# CH32V307VCT6-R1.net
KiCad netlist of a schematic drawn in Altium Designer
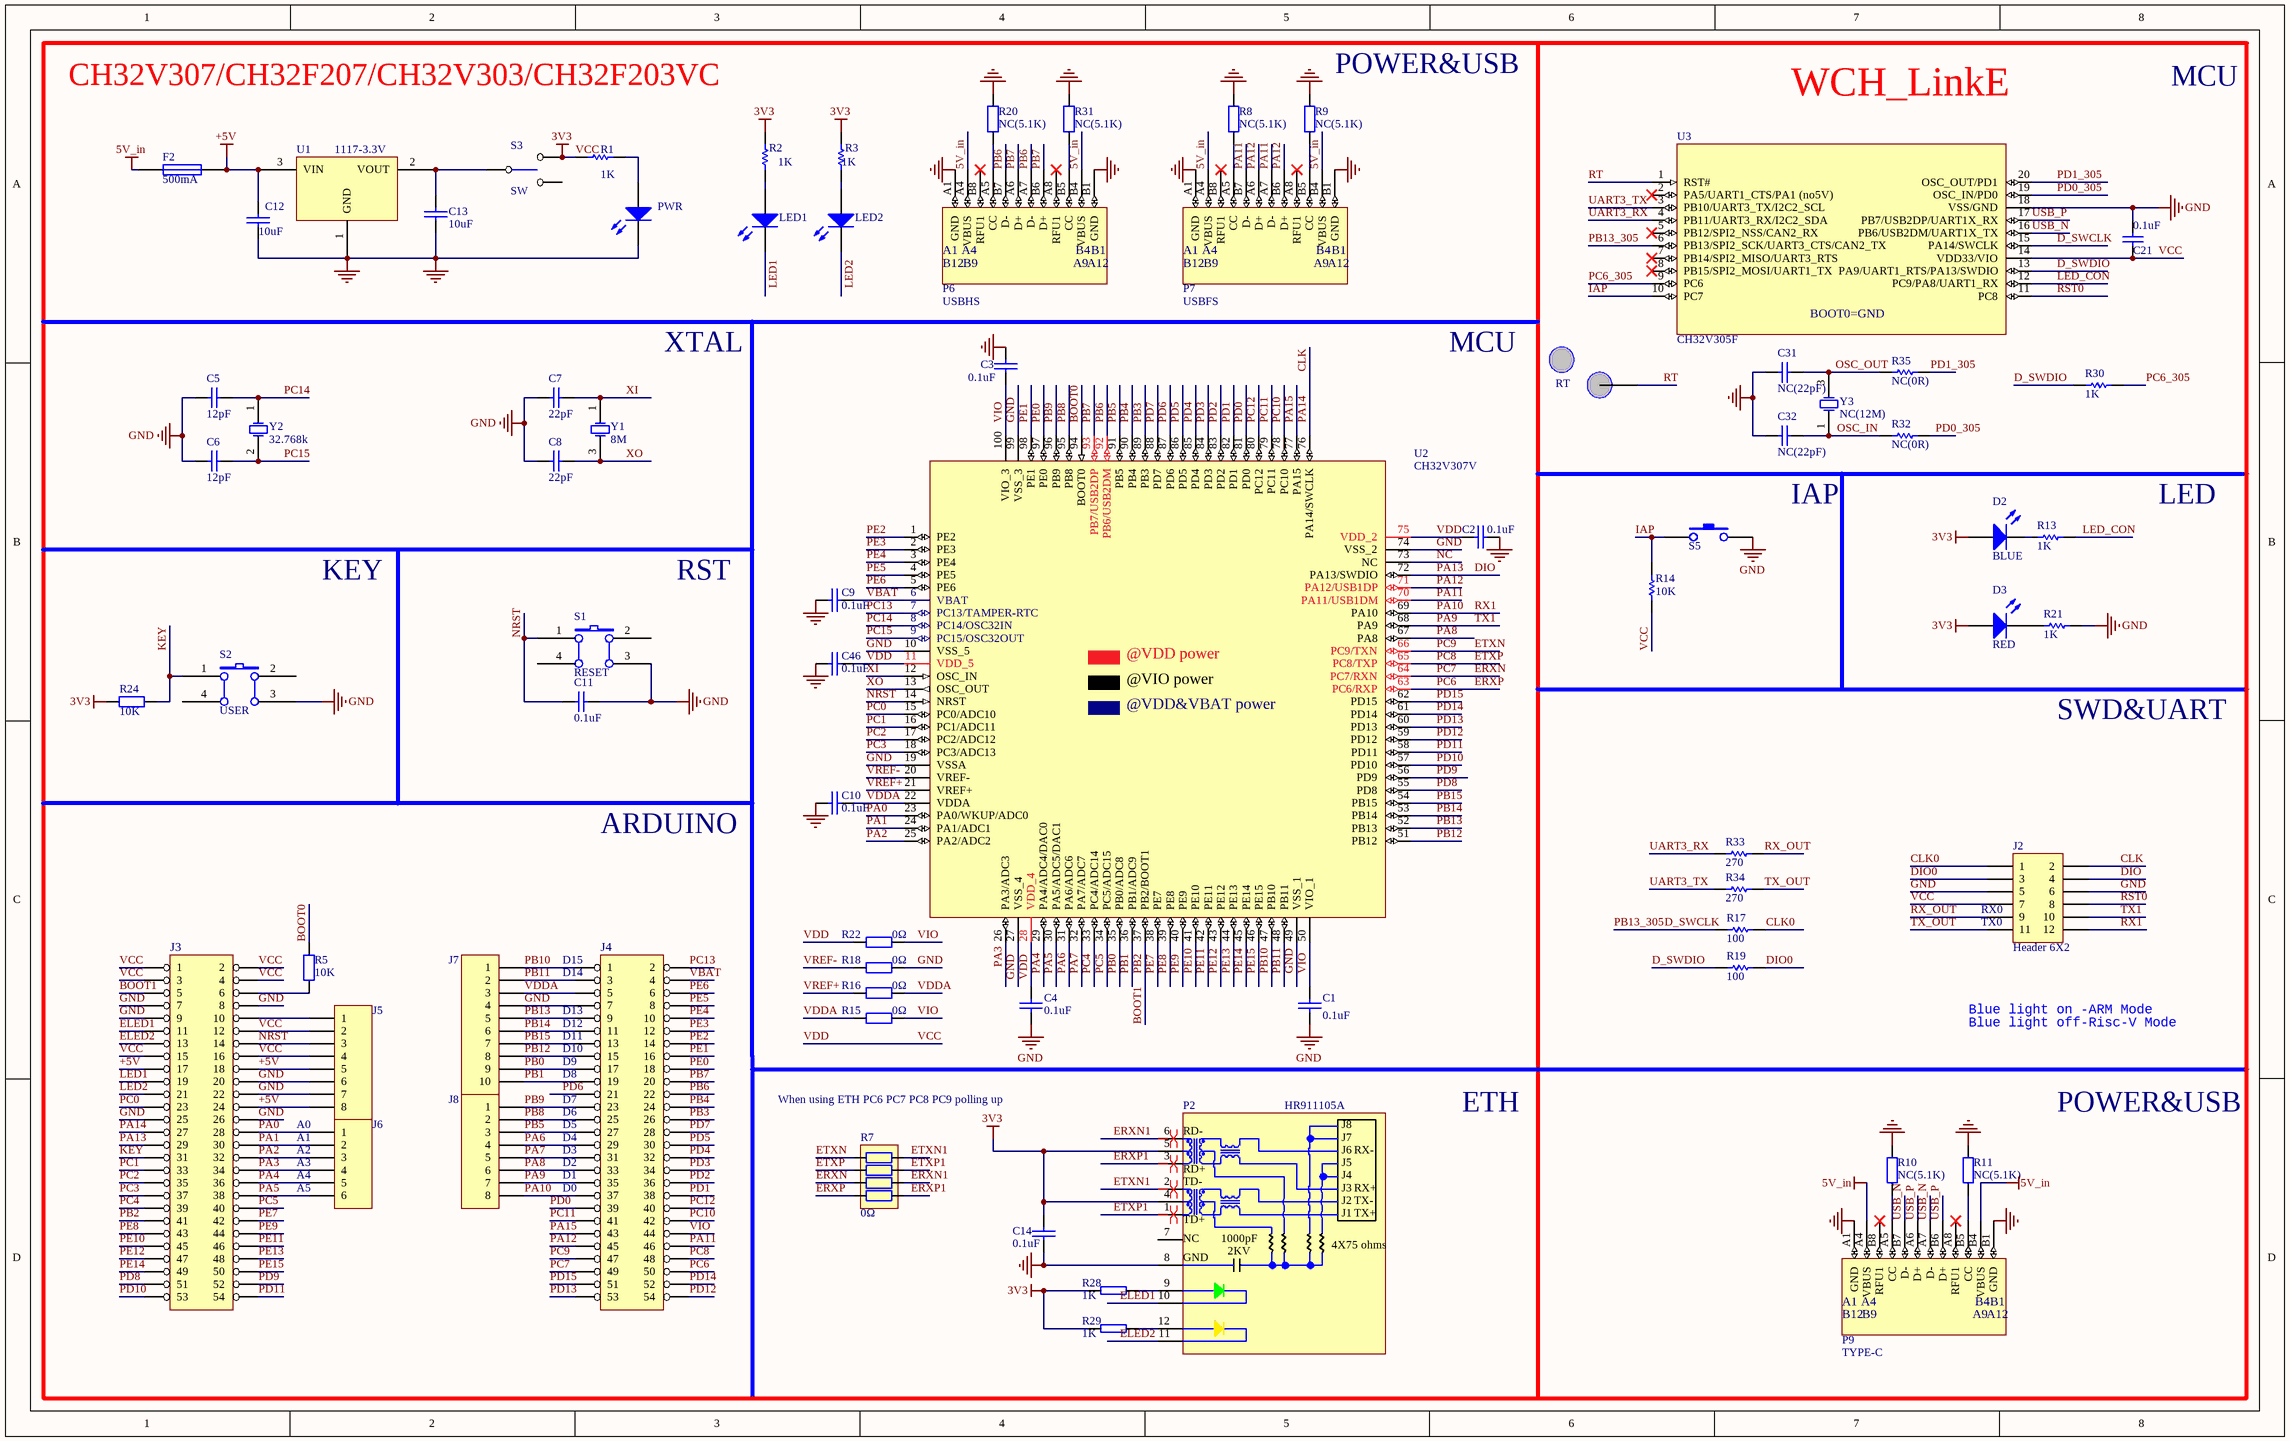
[diagram p0: CH32V307VCT6-R1.SchDoc]

(export (version "E")
  (design (tool "Eeschema 10.0.6"))
  (components
    (comp (ref "C1")
      (value "0.1uF")
      (footprint "0603_C")
      (description "Capacitor")
      (libsource (lib "*") (part "CAP"))
    )
    (comp (ref "C2")
      (value "0.1uF")
      (footprint "0603_C")
      (description "Capacitor")
      (libsource (lib "*") (part "CAP"))
    )
    (comp (ref "C3")
      (value "0.1uF")
      (footprint "0603_C")
      (description "Capacitor")
      (libsource (lib "*") (part "CAP"))
    )
    (comp (ref "C4")
      (value "0.1uF")
      (footprint "0603_C")
      (description "Capacitor")
      (libsource (lib "*") (part "CAP"))
    )
    (comp (ref "C5")
      (value "12pF")
      (footprint "0603_C")
      (description "Capacitor")
      (libsource (lib "Miscellaneous Devices") (part "Cap"))
    )
    (comp (ref "C6")
      (value "12pF")
      (footprint "0603_C")
      (description "Capacitor")
      (libsource (lib "Miscellaneous Devices") (part "Cap"))
    )
    (comp (ref "C7")
      (value "22pF")
      (footprint "0603_C")
      (description "Capacitor")
      (libsource (lib "Miscellaneous Devices") (part "Cap"))
    )
    (comp (ref "C8")
      (value "22pF")
      (footprint "0603_C")
      (description "Capacitor")
      (libsource (lib "Miscellaneous Devices") (part "Cap"))
    )
    (comp (ref "C9")
      (value "0.1uF")
      (footprint "0603_C")
      (description "Capacitor")
      (libsource (lib "*") (part "CAP"))
    )
    (comp (ref "C10")
      (value "0.1uF")
      (footprint "0603_C")
      (description "Capacitor")
      (libsource (lib "*") (part "CAP"))
    )
    (comp (ref "C11")
      (value "0.1uF")
      (footprint "0603_C")
      (description "Capacitor")
      (libsource (lib "Miscellaneous Devices") (part "Cap"))
    )
    (comp (ref "C12")
      (value "10uF")
      (footprint "3216_C")
      (description "Capacitor")
      (libsource (lib "*") (part "CAP"))
    )
    (comp (ref "C13")
      (value "10uF")
      (footprint "3216_C")
      (description "Capacitor")
      (libsource (lib "*") (part "CAP"))
    )
    (comp (ref "C14")
      (value "0.1uF")
      (footprint "0603_C")
      (description "Capacitor")
      (libsource (lib "*") (part "CAP"))
    )
    (comp (ref "C21")
      (value "0.1uF")
      (footprint "0603_C")
      (description "Capacitor")
      (libsource (lib "Miscellaneous Devices") (part "Cap"))
    )
    (comp (ref "C31")
      (value "NC(22pF)")
      (footprint "0603_C")
      (description "Capacitor")
      (libsource (lib "*") (part "Cap"))
    )
    (comp (ref "C32")
      (value "NC(22pF)")
      (footprint "0603_C")
      (description "Capacitor")
      (libsource (lib "*") (part "Cap"))
    )
    (comp (ref "C46")
      (value "0.1uF")
      (footprint "0603_C")
      (description "Capacitor")
      (libsource (lib "*") (part "CAP"))
    )
    (comp (ref "D2")
      (value "BLUE")
      (footprint "0603+")
      (description "Typical RED, GREEN, YELLOW, AMBER GaAs LED")
      (libsource (lib "MYLIB") (part "D0603"))
    )
    (comp (ref "D3")
      (value "RED")
      (footprint "0603+")
      (description "Typical RED, GREEN, YELLOW, AMBER GaAs LED")
      (libsource (lib "MYLIB") (part "D0603"))
    )
    (comp (ref "F2")
      (value "500mA")
      (footprint "0805")
      (description "Fuse")
      (libsource (lib "*") (part "FUSE1"))
    )
    (comp (ref "J2")
      (value "Header 6X2")
      (footprint "IDC12-2.54mm")
      (description "Header, 6-Pin, Dual row")
      (libsource (lib "Miscellaneous Connectors") (part "Header 6X2"))
    )
    (comp (ref "J3")
      (value "HEADER 27x2")
      (footprint "MYPCB:IDC54-2.54MM")
      (description "Header, 27-Pin, Dual row")
      (libsource (lib "wch_sch_others") (part "HEADER 27x2"))
    )
    (comp (ref "J4")
      (value "HEADER 27x2")
      (footprint "MYPCB:IDC54-2.54MM")
      (description "Header, 27-Pin, Dual row")
      (libsource (lib "wch_sch_others") (part "HEADER 27x2"))
    )
    (comp (ref "J5")
      (value "Header 8")
      (footprint "SIP8-2.54mm")
      (description "Header, 8-Pin")
      (libsource (lib "Miscellaneous Connectors") (part "Header 8"))
    )
    (comp (ref "J6")
      (value "Header 6")
      (footprint "SIP6-2.54MM")
      (description "Header, 6-Pin")
      (libsource (lib "Miscellaneous Connectors") (part "Header 6"))
    )
    (comp (ref "J7")
      (value "Header 10")
      (footprint "SIP10-2.54mm")
      (description "Header, 10-Pin")
      (libsource (lib "Miscellaneous Connectors") (part "Header 10"))
    )
    (comp (ref "J8")
      (value "Header 8")
      (footprint "SIP8-2.54mm")
      (description "Header, 8-Pin")
      (libsource (lib "") (part "Header 8_1"))
    )
    (comp (ref "LED1")
      (value "LED1   blue")
      (footprint "0603+")
      (description "Typical INFRARED GaAs LED")
      (libsource (lib "Miscellaneous Devices") (part "LED0"))
    )
    (comp (ref "LED2")
      (value "LED2  blue")
      (footprint "0603+")
      (description "Typical INFRARED GaAs LED")
      (libsource (lib "Miscellaneous Devices") (part "LED0"))
    )
    (comp (ref "P2") (value "HR911105A") (footprint "HR911105A") (libsource (lib "*") (part "HR911105A")))
    (comp (ref "P6")
      (value "USBHS")
      (footprint "TYPE-C-Receptacle-2.0")
      (libsource (lib "*") (part "TYPE-C1"))
    )
    (comp (ref "P7")
      (value "USBFS")
      (footprint "TYPE-C-Receptacle-2.0")
      (libsource (lib "*") (part "TYPE-C1"))
    )
    (comp (ref "P9")
      (value "TYPE-C")
      (footprint "TYPE-C-Receptacle-2.0")
      (libsource (lib "*") (part "TYPE-C1"))
    )
    (comp (ref "PWR")
      (value "POWER  red")
      (footprint "0603+")
      (description "Typical INFRARED GaAs LED")
      (libsource (lib "Miscellaneous Devices") (part "LED0"))
    )
    (comp (ref "R1")
      (value "1K")
      (footprint "0603")
      (description "Semiconductor Resistor")
      (libsource (lib "Miscellaneous Devices") (part "Res Semi"))
    )
    (comp (ref "R2")
      (value "1K")
      (footprint "0603")
      (description "Semiconductor Resistor")
      (libsource (lib "Miscellaneous Devices") (part "Res Semi"))
    )
    (comp (ref "R3")
      (value "1K")
      (footprint "0603")
      (description "Semiconductor Resistor")
      (libsource (lib "Miscellaneous Devices") (part "Res Semi"))
    )
    (comp (ref "R5")
      (value "10K")
      (footprint "0603")
      (description "Resistor")
      (libsource (lib "") (part "Res2_2"))
    )
    (comp (ref "R7")
      (value "0Ω")
      (footprint "RCA-8P4R-0603")
      (description "贴片网络排阻")
      (libsource (lib "wch_sch_others") (part "R-8P4R"))
    )
    (comp (ref "R8")
      (value "NC(5.1K)")
      (footprint "0603")
      (description "Resistor")
      (libsource (lib "") (part "Res2_1"))
    )
    (comp (ref "R9")
      (value "NC(5.1K)")
      (footprint "0603")
      (description "Resistor")
      (libsource (lib "") (part "Res2_1"))
    )
    (comp (ref "R10")
      (value "NC(5.1K)")
      (footprint "0603")
      (description "Resistor")
      (libsource (lib "") (part "Res2_2"))
    )
    (comp (ref "R11")
      (value "NC(5.1K)")
      (footprint "0603")
      (description "Resistor")
      (libsource (lib "") (part "Res2_2"))
    )
    (comp (ref "R13")
      (value "1K")
      (footprint "0603")
      (description "Resistor")
      (libsource (lib "MYLIB") (part "0603-1"))
    )
    (comp (ref "R14")
      (value "10K")
      (footprint "0603")
      (description "Resistor")
      (libsource (lib "MYLIB") (part "0603-1"))
    )
    (comp (ref "R15")
      (value "0Ω")
      (footprint "0603")
      (description "Resistor")
      (libsource (lib "Miscellaneous Devices") (part "Res2"))
    )
    (comp (ref "R16")
      (value "0Ω")
      (footprint "0603")
      (description "Resistor")
      (libsource (lib "Miscellaneous Devices") (part "Res2"))
    )
    (comp (ref "R17")
      (value "100")
      (footprint "0603")
      (description "Resistor")
      (libsource (lib "MYLIB") (part "0603-1"))
    )
    (comp (ref "R18")
      (value "0Ω")
      (footprint "0603")
      (description "Resistor")
      (libsource (lib "Miscellaneous Devices") (part "Res2"))
    )
    (comp (ref "R19")
      (value "100")
      (footprint "0603")
      (description "Resistor")
      (libsource (lib "MYLIB") (part "0603-1"))
    )
    (comp (ref "R20")
      (value "NC(5.1K)")
      (footprint "0603")
      (description "Resistor")
      (libsource (lib "") (part "Res2_1"))
    )
    (comp (ref "R21")
      (value "1K")
      (footprint "0603")
      (description "Resistor")
      (libsource (lib "MYLIB") (part "0603-1"))
    )
    (comp (ref "R22")
      (value "0Ω")
      (footprint "0603")
      (description "Resistor")
      (libsource (lib "Miscellaneous Devices") (part "Res2"))
    )
    (comp (ref "R24")
      (value "10K")
      (footprint "0603")
      (description "Resistor")
      (libsource (lib "Miscellaneous Devices") (part "Res2"))
    )
    (comp (ref "R28") (value "1K") (footprint "0603") (libsource (lib "wch_sch_others") (part "RES")))
    (comp (ref "R29") (value "1K") (footprint "0603") (libsource (lib "wch_sch_others") (part "RES")))
    (comp (ref "R30")
      (value "1K")
      (footprint "0603")
      (description "Resistor")
      (libsource (lib "MYLIB") (part "0603-1"))
    )
    (comp (ref "R31")
      (value "NC(5.1K)")
      (footprint "0603")
      (description "Resistor")
      (libsource (lib "") (part "Res2_1"))
    )
    (comp (ref "R32")
      (value "NC(0R)")
      (footprint "0603")
      (description "Resistor")
      (libsource (lib "MYLIB") (part "0603-1"))
    )
    (comp (ref "R33")
      (value "270")
      (footprint "0603")
      (description "Resistor")
      (libsource (lib "MYLIB") (part "0603-1"))
    )
    (comp (ref "R34")
      (value "270")
      (footprint "0603")
      (description "Resistor")
      (libsource (lib "MYLIB") (part "0603-1"))
    )
    (comp (ref "R35")
      (value "NC(0R)")
      (footprint "0603")
      (description "Resistor")
      (libsource (lib "MYLIB") (part "0603-1"))
    )
    (comp (ref "RT")
      (value "Testpoint")
      (footprint "TESTPOINT1")
      (description "测试点")
      (libsource (lib "wch_sch_others") (part "Testpoint"))
    )
    (comp (ref "S1")
      (value "RESET")
      (footprint "KEYX")
      (description "SE PUSHBUTTON")
      (libsource (lib "Documents") (part "SW PUSHBUTTON"))
    )
    (comp (ref "S2")
      (value "USER")
      (footprint "KEYX")
      (description "SE PUSHBUTTON")
      (libsource (lib "Documents") (part "SW PUSHBUTTON"))
    )
    (comp (ref "S3") (value "SW") (footprint "SW1") (libsource (lib "MYSCH") (part "SW")))
    (comp (ref "S5") (value "KEY") (footprint "贴片按键") (libsource (lib "*") (part "KEY")))
    (comp (ref "U1")
      (value "1117-3.3V")
      (footprint "SOT-223")
      (libsource (lib "wch_sch_others") (part "1117-3.3V"))
    )
    (comp (ref "U2")
      (value "CH32V307V")
      (footprint "LQFP100")
      (description "RISC-V FPU HD-MCU, 144MHz, USB_480M, USB OTG, 1000M Ethernet MAC, 2*CAN, FSMC+DVP")
      (libsource (lib "CHXXX") (part "CH32V307V"))
    )
    (comp (ref "U3")
      (value "CH32V305F")
      (footprint "TSSOP20")
      (description "RISC-V FPU HD-MCU, 144MHz, USB_480M, CAN, UART*2, SPI")
      (libsource (lib "CHXXX") (part "CH32V305F"))
    )
    (comp (ref "Y1")
      (value "8M")
      (footprint "XT3225")
      (description "Crystal Oscillator")
      (libsource (lib "") (part "XTAL_1"))
    )
    (comp (ref "Y2")
      (value "32.768k")
      (footprint "FC-135")
      (description "Crystal Oscillator")
      (libsource (lib "Miscellaneous Devices") (part "XTAL"))
    )
    (comp (ref "Y3")
      (value "NC(12M)")
      (footprint "XT3225")
      (description "Crystal Oscillator")
      (libsource (lib "*") (part "XTAL"))
    )
  )
  (nets
    (net (code "1") (name "+5V") (class "Default")
      (node (ref "C12") (pin "1") (pinfunction "1_1") (pintype "passive"))
      (node (ref "F2") (pin "2") (pinfunction "2_2") (pintype "passive"))
      (node (ref "J3") (pin "17") (pinfunction "17_17") (pintype "passive"))
      (node (ref "J3") (pin "18") (pinfunction "18_18") (pintype "passive"))
      (node (ref "J3") (pin "24") (pinfunction "24_24") (pintype "passive"))
      (node (ref "J5") (pin "5") (pinfunction "5_5") (pintype "passive"))
      (node (ref "J5") (pin "8") (pinfunction "8_8") (pintype "passive"))
      (node (ref "U1") (pin "3") (pinfunction "VIN_3") (pintype "passive"))
    )
    (net (code "2") (name "/BOOT0") (class "Default")
      (node (ref "R5") (pin "2") (pinfunction "2_2") (pintype "passive"))
      (node (ref "U2") (pin "94") (pinfunction "BOOT0_94") (pintype "input"))
    )
    (net (code "3") (name "/BOOT1") (class "Default")
      (node (ref "J3") (pin "41") (pinfunction "41_41") (pintype "passive"))
      (node (ref "J3") (pin "5") (pinfunction "5_5") (pintype "passive"))
      (node (ref "U2") (pin "37") (pinfunction "PB2/BOOT1_37") (pintype "bidirectional"))
    )
    (net (code "4") (name "/CLK") (class "Default")
      (node (ref "J2") (pin "2") (pinfunction "2_2") (pintype "passive"))
      (node (ref "J3") (pin "27") (pinfunction "27_27") (pintype "passive"))
      (node (ref "U2") (pin "76") (pinfunction "PA14/SWCLK_76") (pintype "bidirectional"))
    )
    (net (code "5") (name "/CLK0") (class "Default")
      (node (ref "J2") (pin "1") (pinfunction "1_1") (pintype "passive"))
      (node (ref "R17") (pin "1") (pinfunction "1_1") (pintype "passive"))
    )
    (net (code "6") (name "/DIO") (class "Default")
      (node (ref "J2") (pin "4") (pinfunction "4_4") (pintype "passive"))
      (node (ref "J3") (pin "29") (pinfunction "29_29") (pintype "passive"))
      (node (ref "U2") (pin "72") (pinfunction "PA13/SWDIO_72") (pintype "bidirectional"))
    )
    (net (code "7") (name "/DIO0") (class "Default")
      (node (ref "J2") (pin "3") (pinfunction "3_3") (pintype "passive"))
      (node (ref "R19") (pin "1") (pinfunction "1_1") (pintype "passive"))
    )
    (net (code "8") (name "/D_SWCLK") (class "Default")
      (node (ref "R17") (pin "2") (pinfunction "2_2") (pintype "passive"))
      (node (ref "U3") (pin "15") (pinfunction "PA14/SWCLK_15") (pintype "bidirectional"))
      (node (ref "U3") (pin "6") (pinfunction "PB13/SPI2_SCK/UART3_CTS/CAN2_TX_6") (pintype "bidirectional"))
    )
    (net (code "9") (name "/D_SWDIO") (class "Default")
      (node (ref "R19") (pin "2") (pinfunction "2_2") (pintype "passive"))
      (node (ref "R30") (pin "1") (pinfunction "1_1") (pintype "passive"))
      (node (ref "U3") (pin "13") (pinfunction "PA9/UART1_RTS/PA13/SWDIO_13") (pintype "bidirectional"))
    )
    (net (code "10") (name "/ELED1") (class "Default")
      (node (ref "J3") (pin "11") (pinfunction "11_11") (pintype "passive"))
      (node (ref "P2") (pin "10") (pintype "passive"))
    )
    (net (code "11") (name "/ELED2") (class "Default")
      (node (ref "J3") (pin "13") (pinfunction "13_13") (pintype "passive"))
      (node (ref "P2") (pin "11") (pintype "passive"))
    )
    (net (code "12") (name "/ERXN") (class "Default")
      (node (ref "J4") (pin "49") (pinfunction "49_49") (pintype "passive"))
      (node (ref "R7") (pin "3") (pinfunction "3_3") (pintype "passive"))
      (node (ref "U2") (pin "64") (pinfunction "PC7/RXN_64") (pintype "bidirectional"))
    )
    (net (code "13") (name "/ERXN1") (class "Default")
      (node (ref "P2") (pin "6") (pintype "passive"))
      (node (ref "R7") (pin "6") (pinfunction "6_6") (pintype "passive"))
    )
    (net (code "14") (name "/ERXP") (class "Default")
      (node (ref "J4") (pin "50") (pinfunction "50_50") (pintype "passive"))
      (node (ref "R7") (pin "4") (pinfunction "4_4") (pintype "passive"))
      (node (ref "U2") (pin "63") (pinfunction "PC6/RXP_63") (pintype "bidirectional"))
    )
    (net (code "15") (name "/ERXP1") (class "Default")
      (node (ref "P2") (pin "3") (pintype "passive"))
      (node (ref "R7") (pin "5") (pinfunction "5_5") (pintype "passive"))
    )
    (net (code "16") (name "/ETXN") (class "Default")
      (node (ref "J4") (pin "47") (pinfunction "47_47") (pintype "passive"))
      (node (ref "R7") (pin "1") (pinfunction "1_1") (pintype "passive"))
      (node (ref "U2") (pin "66") (pinfunction "PC9/TXN_66") (pintype "bidirectional"))
    )
    (net (code "17") (name "/ETXN1") (class "Default")
      (node (ref "P2") (pin "2") (pintype "passive"))
      (node (ref "R7") (pin "8") (pinfunction "8_8") (pintype "passive"))
    )
    (net (code "18") (name "/ETXP") (class "Default")
      (node (ref "J4") (pin "48") (pinfunction "48_48") (pintype "passive"))
      (node (ref "R7") (pin "2") (pinfunction "2_2") (pintype "passive"))
      (node (ref "U2") (pin "65") (pinfunction "PC8/TXP_65") (pintype "bidirectional"))
    )
    (net (code "19") (name "/ETXP1") (class "Default")
      (node (ref "P2") (pin "1") (pintype "passive"))
      (node (ref "R7") (pin "7") (pinfunction "7_7") (pintype "passive"))
    )
    (net (code "20") (name "/IAP") (class "Default")
      (node (ref "R14") (pin "1") (pinfunction "1_1") (pintype "passive"))
      (node (ref "S5") (pin "1") (pinfunction "1_1") (pintype "passive"))
      (node (ref "U3") (pin "10") (pinfunction "PC7_10") (pintype "bidirectional"))
    )
    (net (code "21") (name "/KEY") (class "Default")
      (node (ref "J3") (pin "31") (pinfunction "31_31") (pintype "passive"))
      (node (ref "R24") (pin "1") (pinfunction "1_1") (pintype "passive"))
      (node (ref "S2") (pin "1") (pinfunction "A0_1") (pintype "passive"))
    )
    (net (code "22") (name "/LED1") (class "Default")
      (node (ref "J3") (pin "19") (pinfunction "19_19") (pintype "passive"))
      (node (ref "LED1") (pin "2") (pinfunction "K_2") (pintype "passive"))
    )
    (net (code "23") (name "/LED2") (class "Default")
      (node (ref "J3") (pin "21") (pinfunction "21_21") (pintype "passive"))
      (node (ref "LED2") (pin "2") (pinfunction "K_2") (pintype "passive"))
    )
    (net (code "24") (name "/LED_CON") (class "Default")
      (node (ref "R13") (pin "1") (pinfunction "1_1") (pintype "passive"))
      (node (ref "U3") (pin "12") (pinfunction "PC9/PA8/UART1_RX_12") (pintype "bidirectional"))
    )
    (net (code "25") (name "/NC") (class "Default")
      (node (ref "U2") (pin "73") (pinfunction "NC_73") (pintype "tri_state"))
    )
    (net (code "26") (name "/NRST") (class "Default")
      (node (ref "C11") (pin "2") (pinfunction "2_2") (pintype "passive"))
      (node (ref "J3") (pin "14") (pinfunction "14_14") (pintype "passive"))
      (node (ref "J5") (pin "3") (pinfunction "3_3") (pintype "passive"))
      (node (ref "S1") (pin "1") (pinfunction "A0_1") (pintype "passive"))
      (node (ref "U2") (pin "14") (pinfunction "NRST_14") (pintype "input"))
    )
    (net (code "27") (name "/OSC_IN") (class "Default")
      (node (ref "C32") (pin "2") (pinfunction "2_2") (pintype "passive"))
      (node (ref "R32") (pin "2") (pinfunction "2_2") (pintype "passive"))
      (node (ref "Y3") (pin "1") (pinfunction "OSC1_1") (pintype "passive"))
    )
    (net (code "28") (name "/OSC_OUT") (class "Default")
      (node (ref "C31") (pin "2") (pinfunction "2_2") (pintype "passive"))
      (node (ref "R35") (pin "2") (pinfunction "2_2") (pintype "passive"))
      (node (ref "Y3") (pin "3") (pinfunction "OSC2_3") (pintype "passive"))
    )
    (net (code "29") (name "/PA0") (class "Default")
      (node (ref "J3") (pin "28") (pinfunction "28_28") (pintype "passive"))
      (node (ref "J6") (pin "1") (pinfunction "1_1") (pintype "passive"))
      (node (ref "U2") (pin "23") (pinfunction "PA0/WKUP/ADC0_23") (pintype "bidirectional"))
    )
    (net (code "30") (name "/PA1") (class "Default")
      (node (ref "J3") (pin "30") (pinfunction "30_30") (pintype "passive"))
      (node (ref "J6") (pin "2") (pinfunction "2_2") (pintype "passive"))
      (node (ref "U2") (pin "24") (pinfunction "PA1/ADC1_24") (pintype "bidirectional"))
    )
    (net (code "31") (name "/PA2") (class "Default")
      (node (ref "J3") (pin "32") (pinfunction "32_32") (pintype "passive"))
      (node (ref "J6") (pin "3") (pinfunction "3_3") (pintype "passive"))
      (node (ref "U2") (pin "25") (pinfunction "PA2/ADC2_25") (pintype "bidirectional"))
    )
    (net (code "32") (name "/PA3") (class "Default")
      (node (ref "J3") (pin "34") (pinfunction "34_34") (pintype "passive"))
      (node (ref "J6") (pin "4") (pinfunction "4_4") (pintype "passive"))
      (node (ref "U2") (pin "26") (pinfunction "PA3/ADC3_26") (pintype "bidirectional"))
    )
    (net (code "33") (name "/PA4") (class "Default")
      (node (ref "J3") (pin "36") (pinfunction "36_36") (pintype "passive"))
      (node (ref "J6") (pin "5") (pinfunction "5_5") (pintype "passive"))
      (node (ref "U2") (pin "29") (pinfunction "PA4/ADC4/DAC0_29") (pintype "bidirectional"))
    )
    (net (code "34") (name "/PA5") (class "Default")
      (node (ref "J3") (pin "38") (pinfunction "38_38") (pintype "passive"))
      (node (ref "J6") (pin "6") (pinfunction "6_6") (pintype "passive"))
      (node (ref "U2") (pin "30") (pinfunction "PA5/ADC5/DAC1_30") (pintype "bidirectional"))
    )
    (net (code "35") (name "/PA6") (class "Default")
      (node (ref "J4") (pin "29") (pinfunction "29_29") (pintype "passive"))
      (node (ref "J8") (pin "4") (pinfunction "4_4") (pintype "passive"))
      (node (ref "U2") (pin "31") (pinfunction "PA6/ADC6_31") (pintype "bidirectional"))
    )
    (net (code "36") (name "/PA7") (class "Default")
      (node (ref "J4") (pin "31") (pinfunction "31_31") (pintype "passive"))
      (node (ref "J8") (pin "5") (pinfunction "5_5") (pintype "passive"))
      (node (ref "U2") (pin "32") (pinfunction "PA7/ADC7_32") (pintype "bidirectional"))
    )
    (net (code "37") (name "/PA8") (class "Default")
      (node (ref "J4") (pin "33") (pinfunction "33_33") (pintype "passive"))
      (node (ref "J8") (pin "6") (pinfunction "6_6") (pintype "passive"))
      (node (ref "U2") (pin "67") (pinfunction "PA8_67") (pintype "bidirectional"))
    )
    (net (code "38") (name "/PA9") (class "Default")
      (node (ref "J2") (pin "10") (pinfunction "10_10") (pintype "passive"))
      (node (ref "J4") (pin "35") (pinfunction "35_35") (pintype "passive"))
      (node (ref "J8") (pin "7") (pinfunction "7_7") (pintype "passive"))
      (node (ref "U2") (pin "68") (pinfunction "PA9_68") (pintype "bidirectional"))
    )
    (net (code "39") (name "/PA10") (class "Default")
      (node (ref "J2") (pin "12") (pinfunction "12_12") (pintype "passive"))
      (node (ref "J4") (pin "37") (pinfunction "37_37") (pintype "passive"))
      (node (ref "J8") (pin "8") (pinfunction "8_8") (pintype "passive"))
      (node (ref "U2") (pin "69") (pinfunction "PA10_69") (pintype "bidirectional"))
    )
    (net (code "40") (name "/PA11") (class "Default")
      (node (ref "J4") (pin "46") (pinfunction "46_46") (pintype "passive"))
      (node (ref "P7") (pin "A7") (pinfunction "D-_A7") (pintype "bidirectional"))
      (node (ref "P7") (pin "B7") (pinfunction "D-_B7") (pintype "bidirectional"))
      (node (ref "U2") (pin "70") (pinfunction "PA11/USB1DM_70") (pintype "bidirectional"))
    )
    (net (code "41") (name "/PA12") (class "Default")
      (node (ref "J4") (pin "45") (pinfunction "45_45") (pintype "passive"))
      (node (ref "P7") (pin "A6") (pinfunction "D+_A6") (pintype "bidirectional"))
      (node (ref "P7") (pin "B6") (pinfunction "D+_B6") (pintype "bidirectional"))
      (node (ref "U2") (pin "71") (pinfunction "PA12/USB1DP_71") (pintype "bidirectional"))
    )
    (net (code "42") (name "/PA15") (class "Default")
      (node (ref "J4") (pin "43") (pinfunction "43_43") (pintype "passive"))
      (node (ref "U2") (pin "77") (pinfunction "PA15_77") (pintype "bidirectional"))
    )
    (net (code "43") (name "/PB0") (class "Default")
      (node (ref "J4") (pin "17") (pinfunction "17_17") (pintype "passive"))
      (node (ref "J7") (pin "9") (pinfunction "9_9") (pintype "passive"))
      (node (ref "U2") (pin "35") (pinfunction "PB0/ADC8_35") (pintype "bidirectional"))
    )
    (net (code "44") (name "/PB1") (class "Default")
      (node (ref "J4") (pin "19") (pinfunction "19_19") (pintype "passive"))
      (node (ref "J7") (pin "10") (pinfunction "10_10") (pintype "passive"))
      (node (ref "U2") (pin "36") (pinfunction "PB1/ADC9_36") (pintype "bidirectional"))
    )
    (net (code "45") (name "/PB3") (class "Default")
      (node (ref "J4") (pin "26") (pinfunction "26_26") (pintype "passive"))
      (node (ref "U2") (pin "89") (pinfunction "PB3_89") (pintype "bidirectional"))
    )
    (net (code "46") (name "/PB4") (class "Default")
      (node (ref "J4") (pin "24") (pinfunction "24_24") (pintype "passive"))
      (node (ref "U2") (pin "90") (pinfunction "PB4_90") (pintype "bidirectional"))
    )
    (net (code "47") (name "/PB5") (class "Default")
      (node (ref "J4") (pin "27") (pinfunction "27_27") (pintype "passive"))
      (node (ref "J8") (pin "3") (pinfunction "3_3") (pintype "passive"))
      (node (ref "U2") (pin "91") (pinfunction "PB5_91") (pintype "bidirectional"))
    )
    (net (code "48") (name "/PB6") (class "Default")
      (node (ref "J4") (pin "22") (pinfunction "22_22") (pintype "passive"))
      (node (ref "P6") (pin "A7") (pinfunction "D-_A7") (pintype "bidirectional"))
      (node (ref "P6") (pin "B7") (pinfunction "D-_B7") (pintype "bidirectional"))
      (node (ref "U2") (pin "92") (pinfunction "PB6/USB2DM_92") (pintype "bidirectional"))
    )
    (net (code "49") (name "/PB7") (class "Default")
      (node (ref "J4") (pin "20") (pinfunction "20_20") (pintype "passive"))
      (node (ref "P6") (pin "A6") (pinfunction "D+_A6") (pintype "bidirectional"))
      (node (ref "P6") (pin "B6") (pinfunction "D+_B6") (pintype "bidirectional"))
      (node (ref "U2") (pin "93") (pinfunction "PB7/USB2DP_93") (pintype "bidirectional"))
    )
    (net (code "50") (name "/PB8") (class "Default")
      (node (ref "J4") (pin "25") (pinfunction "25_25") (pintype "passive"))
      (node (ref "J8") (pin "2") (pinfunction "2_2") (pintype "passive"))
      (node (ref "U2") (pin "95") (pinfunction "PB8_95") (pintype "bidirectional"))
    )
    (net (code "51") (name "/PB9") (class "Default")
      (node (ref "J4") (pin "23") (pinfunction "23_23") (pintype "passive"))
      (node (ref "J8") (pin "1") (pinfunction "1_1") (pintype "passive"))
      (node (ref "U2") (pin "96") (pinfunction "PB9_96") (pintype "bidirectional"))
    )
    (net (code "52") (name "/PB10") (class "Default")
      (node (ref "J4") (pin "1") (pinfunction "1_1") (pintype "passive"))
      (node (ref "J7") (pin "1") (pinfunction "1_1") (pintype "passive"))
      (node (ref "U2") (pin "47") (pinfunction "PB10_47") (pintype "bidirectional"))
    )
    (net (code "53") (name "/PB11") (class "Default")
      (node (ref "J4") (pin "3") (pinfunction "3_3") (pintype "passive"))
      (node (ref "J7") (pin "2") (pinfunction "2_2") (pintype "passive"))
      (node (ref "U2") (pin "48") (pinfunction "PB11_48") (pintype "bidirectional"))
    )
    (net (code "54") (name "/PB12") (class "Default")
      (node (ref "J4") (pin "15") (pinfunction "15_15") (pintype "passive"))
      (node (ref "J7") (pin "8") (pinfunction "8_8") (pintype "passive"))
      (node (ref "U2") (pin "51") (pinfunction "PB12_51") (pintype "bidirectional"))
    )
    (net (code "55") (name "/PB13") (class "Default")
      (node (ref "J4") (pin "9") (pinfunction "9_9") (pintype "passive"))
      (node (ref "J7") (pin "5") (pinfunction "5_5") (pintype "passive"))
      (node (ref "U2") (pin "52") (pinfunction "PB13_52") (pintype "bidirectional"))
    )
    (net (code "56") (name "/PB14") (class "Default")
      (node (ref "J4") (pin "11") (pinfunction "11_11") (pintype "passive"))
      (node (ref "J7") (pin "6") (pinfunction "6_6") (pintype "passive"))
      (node (ref "U2") (pin "53") (pinfunction "PB14_53") (pintype "bidirectional"))
    )
    (net (code "57") (name "/PB15") (class "Default")
      (node (ref "J4") (pin "13") (pinfunction "13_13") (pintype "passive"))
      (node (ref "J7") (pin "7") (pinfunction "7_7") (pintype "passive"))
      (node (ref "U2") (pin "54") (pinfunction "PB15_54") (pintype "bidirectional"))
    )
    (net (code "58") (name "/PC0") (class "Default")
      (node (ref "J3") (pin "23") (pinfunction "23_23") (pintype "passive"))
      (node (ref "U2") (pin "15") (pinfunction "PC0/ADC10_15") (pintype "bidirectional"))
    )
    (net (code "59") (name "/PC1") (class "Default")
      (node (ref "J3") (pin "33") (pinfunction "33_33") (pintype "passive"))
      (node (ref "U2") (pin "16") (pinfunction "PC1/ADC11_16") (pintype "bidirectional"))
    )
    (net (code "60") (name "/PC2") (class "Default")
      (node (ref "J3") (pin "35") (pinfunction "35_35") (pintype "passive"))
      (node (ref "U2") (pin "17") (pinfunction "PC2/ADC12_17") (pintype "bidirectional"))
    )
    (net (code "61") (name "/PC3") (class "Default")
      (node (ref "J3") (pin "37") (pinfunction "37_37") (pintype "passive"))
      (node (ref "U2") (pin "18") (pinfunction "PC3/ADC13_18") (pintype "bidirectional"))
    )
    (net (code "62") (name "/PC4") (class "Default")
      (node (ref "J3") (pin "39") (pinfunction "39_39") (pintype "passive"))
      (node (ref "U2") (pin "33") (pinfunction "PC4/ADC14_33") (pintype "bidirectional"))
    )
    (net (code "63") (name "/PC5") (class "Default")
      (node (ref "J3") (pin "40") (pinfunction "40_40") (pintype "passive"))
      (node (ref "U2") (pin "34") (pinfunction "PC5/ADC15_34") (pintype "bidirectional"))
    )
    (net (code "64") (name "/PC6_305") (class "Default")
      (node (ref "R30") (pin "2") (pinfunction "2_2") (pintype "passive"))
      (node (ref "U3") (pin "9") (pinfunction "PC6_9") (pintype "bidirectional"))
    )
    (net (code "65") (name "/PC10") (class "Default")
      (node (ref "J4") (pin "42") (pinfunction "42_42") (pintype "passive"))
      (node (ref "U2") (pin "78") (pinfunction "PC10_78") (pintype "bidirectional"))
    )
    (net (code "66") (name "/PC11") (class "Default")
      (node (ref "J4") (pin "41") (pinfunction "41_41") (pintype "passive"))
      (node (ref "U2") (pin "79") (pinfunction "PC11_79") (pintype "bidirectional"))
    )
    (net (code "67") (name "/PC12") (class "Default")
      (node (ref "J4") (pin "40") (pinfunction "40_40") (pintype "passive"))
      (node (ref "U2") (pin "80") (pinfunction "PC12_80") (pintype "bidirectional"))
    )
    (net (code "68") (name "/PC13") (class "Default")
      (node (ref "J4") (pin "2") (pinfunction "2_2") (pintype "passive"))
      (node (ref "U2") (pin "7") (pinfunction "PC13/TAMPER-RTC_7") (pintype "bidirectional"))
    )
    (net (code "69") (name "/PC14") (class "Default")
      (node (ref "C5") (pin "1") (pinfunction "1_1") (pintype "passive"))
      (node (ref "U2") (pin "8") (pinfunction "PC14/OSC32IN_8") (pintype "bidirectional"))
      (node (ref "Y2") (pin "1") (pinfunction "OSC1_1") (pintype "passive"))
    )
    (net (code "70") (name "/PC15") (class "Default")
      (node (ref "C6") (pin "1") (pinfunction "1_1") (pintype "passive"))
      (node (ref "U2") (pin "9") (pinfunction "PC15/OSC32OUT_9") (pintype "bidirectional"))
      (node (ref "Y2") (pin "2") (pinfunction "OSC2_2") (pintype "passive"))
    )
    (net (code "71") (name "/PD0") (class "Default")
      (node (ref "J4") (pin "39") (pinfunction "39_39") (pintype "passive"))
      (node (ref "U2") (pin "81") (pinfunction "PD0_81") (pintype "bidirectional"))
    )
    (net (code "72") (name "/PD0_305") (class "Default")
      (node (ref "R32") (pin "1") (pinfunction "1_1") (pintype "passive"))
      (node (ref "U3") (pin "19") (pinfunction "OSC_IN/PD0_19") (pintype "bidirectional"))
    )
    (net (code "73") (name "/PD1") (class "Default")
      (node (ref "J4") (pin "38") (pinfunction "38_38") (pintype "passive"))
      (node (ref "U2") (pin "82") (pinfunction "PD1_82") (pintype "bidirectional"))
    )
    (net (code "74") (name "/PD1_305") (class "Default")
      (node (ref "R35") (pin "1") (pinfunction "1_1") (pintype "passive"))
      (node (ref "U3") (pin "20") (pinfunction "OSC_OUT/PD1_20") (pintype "bidirectional"))
    )
    (net (code "75") (name "/PD2") (class "Default")
      (node (ref "J4") (pin "36") (pinfunction "36_36") (pintype "passive"))
      (node (ref "U2") (pin "83") (pinfunction "PD2_83") (pintype "bidirectional"))
    )
    (net (code "76") (name "/PD3") (class "Default")
      (node (ref "J4") (pin "34") (pinfunction "34_34") (pintype "passive"))
      (node (ref "U2") (pin "84") (pinfunction "PD3_84") (pintype "bidirectional"))
    )
    (net (code "77") (name "/PD4") (class "Default")
      (node (ref "J4") (pin "32") (pinfunction "32_32") (pintype "passive"))
      (node (ref "U2") (pin "85") (pinfunction "PD4_85") (pintype "bidirectional"))
    )
    (net (code "78") (name "/PD5") (class "Default")
      (node (ref "J4") (pin "30") (pinfunction "30_30") (pintype "passive"))
      (node (ref "U2") (pin "86") (pinfunction "PD5_86") (pintype "bidirectional"))
    )
    (net (code "79") (name "/PD6") (class "Default")
      (node (ref "J4") (pin "21") (pinfunction "21_21") (pintype "passive"))
      (node (ref "U2") (pin "87") (pinfunction "PD6_87") (pintype "bidirectional"))
    )
    (net (code "80") (name "/PD7") (class "Default")
      (node (ref "J4") (pin "28") (pinfunction "28_28") (pintype "passive"))
      (node (ref "U2") (pin "88") (pinfunction "PD7_88") (pintype "bidirectional"))
    )
    (net (code "81") (name "/PD8") (class "Default")
      (node (ref "J3") (pin "51") (pinfunction "51_51") (pintype "passive"))
      (node (ref "U2") (pin "55") (pinfunction "PD8_55") (pintype "bidirectional"))
    )
    (net (code "82") (name "/PD9") (class "Default")
      (node (ref "J3") (pin "52") (pinfunction "52_52") (pintype "passive"))
      (node (ref "U2") (pin "56") (pinfunction "PD9_56") (pintype "bidirectional"))
    )
    (net (code "83") (name "/PD10") (class "Default")
      (node (ref "J3") (pin "53") (pinfunction "53_53") (pintype "passive"))
      (node (ref "U2") (pin "57") (pinfunction "PD10_57") (pintype "bidirectional"))
    )
    (net (code "84") (name "/PD11") (class "Default")
      (node (ref "J3") (pin "54") (pinfunction "54_54") (pintype "passive"))
      (node (ref "U2") (pin "58") (pinfunction "PD11_58") (pintype "bidirectional"))
    )
    (net (code "85") (name "/PD12") (class "Default")
      (node (ref "J4") (pin "54") (pinfunction "54_54") (pintype "passive"))
      (node (ref "U2") (pin "59") (pinfunction "PD12_59") (pintype "bidirectional"))
    )
    (net (code "86") (name "/PD13") (class "Default")
      (node (ref "J4") (pin "53") (pinfunction "53_53") (pintype "passive"))
      (node (ref "U2") (pin "60") (pinfunction "PD13_60") (pintype "bidirectional"))
    )
    (net (code "87") (name "/PD14") (class "Default")
      (node (ref "J4") (pin "52") (pinfunction "52_52") (pintype "passive"))
      (node (ref "U2") (pin "61") (pinfunction "PD14_61") (pintype "bidirectional"))
    )
    (net (code "88") (name "/PD15") (class "Default")
      (node (ref "J4") (pin "51") (pinfunction "51_51") (pintype "passive"))
      (node (ref "U2") (pin "62") (pinfunction "PD15_62") (pintype "bidirectional"))
    )
    (net (code "89") (name "/PE0") (class "Default")
      (node (ref "J4") (pin "18") (pinfunction "18_18") (pintype "passive"))
      (node (ref "U2") (pin "97") (pinfunction "PE0_97") (pintype "bidirectional"))
    )
    (net (code "90") (name "/PE1") (class "Default")
      (node (ref "J4") (pin "16") (pinfunction "16_16") (pintype "passive"))
      (node (ref "U2") (pin "98") (pinfunction "PE1_98") (pintype "bidirectional"))
    )
    (net (code "91") (name "/PE2") (class "Default")
      (node (ref "J4") (pin "14") (pinfunction "14_14") (pintype "passive"))
      (node (ref "U2") (pin "1") (pinfunction "PE2_1") (pintype "bidirectional"))
    )
    (net (code "92") (name "/PE3") (class "Default")
      (node (ref "J4") (pin "12") (pinfunction "12_12") (pintype "passive"))
      (node (ref "U2") (pin "2") (pinfunction "PE3_2") (pintype "bidirectional"))
    )
    (net (code "93") (name "/PE4") (class "Default")
      (node (ref "J4") (pin "10") (pinfunction "10_10") (pintype "passive"))
      (node (ref "U2") (pin "3") (pinfunction "PE4_3") (pintype "bidirectional"))
    )
    (net (code "94") (name "/PE5") (class "Default")
      (node (ref "J4") (pin "8") (pinfunction "8_8") (pintype "passive"))
      (node (ref "U2") (pin "4") (pinfunction "PE5_4") (pintype "bidirectional"))
    )
    (net (code "95") (name "/PE6") (class "Default")
      (node (ref "J4") (pin "6") (pinfunction "6_6") (pintype "passive"))
      (node (ref "U2") (pin "5") (pinfunction "PE6_5") (pintype "bidirectional"))
    )
    (net (code "96") (name "/PE7") (class "Default")
      (node (ref "J3") (pin "42") (pinfunction "42_42") (pintype "passive"))
      (node (ref "U2") (pin "38") (pinfunction "PE7_38") (pintype "bidirectional"))
    )
    (net (code "97") (name "/PE8") (class "Default")
      (node (ref "J3") (pin "43") (pinfunction "43_43") (pintype "passive"))
      (node (ref "U2") (pin "39") (pinfunction "PE8_39") (pintype "bidirectional"))
    )
    (net (code "98") (name "/PE9") (class "Default")
      (node (ref "J3") (pin "44") (pinfunction "44_44") (pintype "passive"))
      (node (ref "U2") (pin "40") (pinfunction "PE9_40") (pintype "bidirectional"))
    )
    (net (code "99") (name "/PE10") (class "Default")
      (node (ref "J3") (pin "45") (pinfunction "45_45") (pintype "passive"))
      (node (ref "U2") (pin "41") (pinfunction "PE10_41") (pintype "bidirectional"))
    )
    (net (code "100") (name "/PE11") (class "Default")
      (node (ref "J3") (pin "46") (pinfunction "46_46") (pintype "passive"))
      (node (ref "U2") (pin "42") (pinfunction "PE11_42") (pintype "bidirectional"))
    )
    (net (code "101") (name "/PE12") (class "Default")
      (node (ref "J3") (pin "47") (pinfunction "47_47") (pintype "passive"))
      (node (ref "U2") (pin "43") (pinfunction "PE12_43") (pintype "bidirectional"))
    )
    (net (code "102") (name "/PE13") (class "Default")
      (node (ref "J3") (pin "48") (pinfunction "48_48") (pintype "passive"))
      (node (ref "U2") (pin "44") (pinfunction "PE13_44") (pintype "bidirectional"))
    )
    (net (code "103") (name "/PE14") (class "Default")
      (node (ref "J3") (pin "49") (pinfunction "49_49") (pintype "passive"))
      (node (ref "U2") (pin "45") (pinfunction "PE14_45") (pintype "bidirectional"))
    )
    (net (code "104") (name "/PE15") (class "Default")
      (node (ref "J3") (pin "50") (pinfunction "50_50") (pintype "passive"))
      (node (ref "U2") (pin "46") (pinfunction "PE15_46") (pintype "bidirectional"))
    )
    (net (code "105") (name "/RST0") (class "Default")
      (node (ref "J2") (pin "8") (pinfunction "8_8") (pintype "passive"))
      (node (ref "U3") (pin "11") (pinfunction "PC8_11") (pintype "bidirectional"))
    )
    (net (code "106") (name "/RT") (class "Default")
      (node (ref "RT") (pin "1") (pinfunction "point_1") (pintype "passive"))
      (node (ref "U3") (pin "1") (pinfunction "RST#_1") (pintype "input"))
    )
    (net (code "107") (name "/RX_OUT") (class "Default")
      (node (ref "J2") (pin "9") (pinfunction "9_9") (pintype "passive"))
      (node (ref "R33") (pin "1") (pinfunction "1_1") (pintype "passive"))
    )
    (net (code "108") (name "/TX_OUT") (class "Default")
      (node (ref "J2") (pin "11") (pinfunction "11_11") (pintype "passive"))
      (node (ref "R34") (pin "1") (pinfunction "1_1") (pintype "passive"))
    )
    (net (code "109") (name "/UART3_RX") (class "Default")
      (node (ref "R33") (pin "2") (pinfunction "2_2") (pintype "passive"))
      (node (ref "U3") (pin "4") (pinfunction "PB11/UART3_RX/I2C2_SDA_4") (pintype "bidirectional"))
    )
    (net (code "110") (name "/UART3_TX") (class "Default")
      (node (ref "R34") (pin "2") (pinfunction "2_2") (pintype "passive"))
      (node (ref "U3") (pin "3") (pinfunction "PB10/UART3_TX/I2C2_SCL_3") (pintype "bidirectional"))
    )
    (net (code "111") (name "/USB_N") (class "Default")
      (node (ref "P9") (pin "A7") (pinfunction "D-_A7") (pintype "bidirectional"))
      (node (ref "P9") (pin "B7") (pinfunction "D-_B7") (pintype "bidirectional"))
      (node (ref "U3") (pin "16") (pinfunction "PB6/USB2DM/UART1X_TX_16") (pintype "bidirectional"))
    )
    (net (code "112") (name "/USB_P") (class "Default")
      (node (ref "P9") (pin "A6") (pinfunction "D+_A6") (pintype "bidirectional"))
      (node (ref "P9") (pin "B6") (pinfunction "D+_B6") (pintype "bidirectional"))
      (node (ref "U3") (pin "17") (pinfunction "PB7/USB2DP/UART1X_RX_17") (pintype "bidirectional"))
    )
    (net (code "113") (name "/VBAT") (class "Default")
      (node (ref "C9") (pin "2") (pinfunction "2_2") (pintype "passive"))
      (node (ref "J4") (pin "4") (pinfunction "4_4") (pintype "passive"))
      (node (ref "U2") (pin "6") (pinfunction "VBAT_6") (pintype "power_in"))
    )
    (net (code "114") (name "/VDDA") (class "Default")
      (node (ref "C10") (pin "2") (pinfunction "2_2") (pintype "passive"))
      (node (ref "J4") (pin "5") (pinfunction "5_5") (pintype "passive"))
      (node (ref "J7") (pin "3") (pinfunction "3_3") (pintype "passive"))
      (node (ref "R15") (pin "2") (pinfunction "2_2") (pintype "passive"))
      (node (ref "R16") (pin "1") (pinfunction "1_1") (pintype "passive"))
      (node (ref "U2") (pin "22") (pinfunction "VDDA_22") (pintype "power_in"))
    )
    (net (code "115") (name "/VIO") (class "Default")
      (node (ref "C1") (pin "2") (pinfunction "2_2") (pintype "passive"))
      (node (ref "C3") (pin "1") (pinfunction "1_1") (pintype "passive"))
      (node (ref "J4") (pin "44") (pinfunction "44_44") (pintype "passive"))
      (node (ref "R15") (pin "1") (pinfunction "1_1") (pintype "passive"))
      (node (ref "R22") (pin "1") (pinfunction "1_1") (pintype "passive"))
      (node (ref "U2") (pin "100") (pinfunction "VIO_3_100") (pintype "power_in"))
      (node (ref "U2") (pin "50") (pinfunction "VIO_1_50") (pintype "power_in"))
    )
    (net (code "116") (name "/VREF+") (class "Default")
      (node (ref "R16") (pin "2") (pinfunction "2_2") (pintype "passive"))
      (node (ref "U2") (pin "21") (pinfunction "VREF+_21") (pintype "power_in"))
    )
    (net (code "117") (name "/VREF-") (class "Default")
      (node (ref "R18") (pin "2") (pinfunction "2_2") (pintype "passive"))
      (node (ref "U2") (pin "20") (pinfunction "VREF-_20") (pintype "power_in"))
    )
    (net (code "118") (name "/XI") (class "Default")
      (node (ref "C7") (pin "2") (pinfunction "2_2") (pintype "passive"))
      (node (ref "U2") (pin "12") (pinfunction "OSC_IN_12") (pintype "input"))
      (node (ref "Y1") (pin "1") (pinfunction "OSC1_1") (pintype "passive"))
    )
    (net (code "119") (name "/XO") (class "Default")
      (node (ref "C8") (pin "2") (pinfunction "2_2") (pintype "passive"))
      (node (ref "U2") (pin "13") (pinfunction "OSC_OUT_13") (pintype "output"))
      (node (ref "Y1") (pin "3") (pinfunction "OSC2_3") (pintype "passive"))
    )
    (net (code "120") (name "3V3") (class "Default")
      (node (ref "C14") (pin "2") (pinfunction "2_2") (pintype "passive"))
      (node (ref "C2") (pin "2") (pinfunction "2_2") (pintype "passive"))
      (node (ref "C21") (pin "1") (pinfunction "1_1") (pintype "passive"))
      (node (ref "C4") (pin "2") (pinfunction "2_2") (pintype "passive"))
      (node (ref "C46") (pin "1") (pinfunction "1_1") (pintype "passive"))
      (node (ref "D2") (pin "1") (pinfunction "A_1") (pintype "passive"))
      (node (ref "D3") (pin "1") (pinfunction "A_1") (pintype "passive"))
      (node (ref "J2") (pin "7") (pinfunction "7_7") (pintype "passive"))
      (node (ref "J3") (pin "1") (pinfunction "1_1") (pintype "passive"))
      (node (ref "J3") (pin "12") (pinfunction "12_12") (pintype "passive"))
      (node (ref "J3") (pin "15") (pinfunction "15_15") (pintype "passive"))
      (node (ref "J3") (pin "16") (pinfunction "16_16") (pintype "passive"))
      (node (ref "J3") (pin "2") (pinfunction "2_2") (pintype "passive"))
      (node (ref "J3") (pin "3") (pinfunction "3_3") (pintype "passive"))
      (node (ref "J3") (pin "4") (pinfunction "4_4") (pintype "passive"))
      (node (ref "J5") (pin "2") (pinfunction "2_2") (pintype "passive"))
      (node (ref "J5") (pin "4") (pinfunction "4_4") (pintype "passive"))
      (node (ref "P2") (pin "4") (pintype "passive"))
      (node (ref "P2") (pin "5") (pintype "passive"))
      (node (ref "R1") (pin "2") (pinfunction "2_2") (pintype "passive"))
      (node (ref "R14") (pin "2") (pinfunction "2_2") (pintype "passive"))
      (node (ref "R2") (pin "1") (pinfunction "1_1") (pintype "passive"))
      (node (ref "R22") (pin "2") (pinfunction "2_2") (pintype "passive"))
      (node (ref "R24") (pin "2") (pinfunction "2_2") (pintype "passive"))
      (node (ref "R28") (pin "1") (pintype "passive"))
      (node (ref "R29") (pin "1") (pintype "passive"))
      (node (ref "R3") (pin "1") (pinfunction "1_1") (pintype "passive"))
      (node (ref "S3") (pin "3") (pinfunction "3_3") (pintype "passive"))
      (node (ref "U2") (pin "11") (pinfunction "VDD_5_11") (pintype "power_in"))
      (node (ref "U2") (pin "28") (pinfunction "VDD_4_28") (pintype "power_in"))
      (node (ref "U2") (pin "75") (pinfunction "VDD_2_75") (pintype "power_in"))
      (node (ref "U3") (pin "14") (pinfunction "VDD33/VIO_14") (pintype "power_in"))
    )
    (net (code "121") (name "5V_in") (class "Default")
      (node (ref "F2") (pin "1") (pinfunction "1_1") (pintype "passive"))
      (node (ref "P6") (pin "A4") (pinfunction "VBUS_A4") (pintype "bidirectional"))
      (node (ref "P6") (pin "B4") (pinfunction "VBUS_B4") (pintype "bidirectional"))
      (node (ref "P7") (pin "A4") (pinfunction "VBUS_A4") (pintype "bidirectional"))
      (node (ref "P7") (pin "B4") (pinfunction "VBUS_B4") (pintype "bidirectional"))
      (node (ref "P9") (pin "A4") (pinfunction "VBUS_A4") (pintype "bidirectional"))
      (node (ref "P9") (pin "B4") (pinfunction "VBUS_B4") (pintype "bidirectional"))
    )
    (net (code "122") (name "GND") (class "Default")
      (node (ref "C1") (pin "1") (pinfunction "1_1") (pintype "passive"))
      (node (ref "C10") (pin "1") (pinfunction "1_1") (pintype "passive"))
      (node (ref "C11") (pin "1") (pinfunction "1_1") (pintype "passive"))
      (node (ref "C12") (pin "2") (pinfunction "2_2") (pintype "passive"))
      (node (ref "C13") (pin "2") (pinfunction "2_2") (pintype "passive"))
      (node (ref "C14") (pin "1") (pinfunction "1_1") (pintype "passive"))
      (node (ref "C2") (pin "1") (pinfunction "1_1") (pintype "passive"))
      (node (ref "C21") (pin "2") (pinfunction "2_2") (pintype "passive"))
      (node (ref "C3") (pin "2") (pinfunction "2_2") (pintype "passive"))
      (node (ref "C31") (pin "1") (pinfunction "1_1") (pintype "passive"))
      (node (ref "C32") (pin "1") (pinfunction "1_1") (pintype "passive"))
      (node (ref "C4") (pin "1") (pinfunction "1_1") (pintype "passive"))
      (node (ref "C46") (pin "2") (pinfunction "2_2") (pintype "passive"))
      (node (ref "C5") (pin "2") (pinfunction "2_2") (pintype "passive"))
      (node (ref "C6") (pin "2") (pinfunction "2_2") (pintype "passive"))
      (node (ref "C7") (pin "1") (pinfunction "1_1") (pintype "passive"))
      (node (ref "C8") (pin "1") (pinfunction "1_1") (pintype "passive"))
      (node (ref "C9") (pin "1") (pinfunction "1_1") (pintype "passive"))
      (node (ref "J2") (pin "5") (pinfunction "5_5") (pintype "passive"))
      (node (ref "J2") (pin "6") (pinfunction "6_6") (pintype "passive"))
      (node (ref "J3") (pin "20") (pinfunction "20_20") (pintype "passive"))
      (node (ref "J3") (pin "22") (pinfunction "22_22") (pintype "passive"))
      (node (ref "J3") (pin "25") (pinfunction "25_25") (pintype "passive"))
      (node (ref "J3") (pin "26") (pinfunction "26_26") (pintype "passive"))
      (node (ref "J3") (pin "7") (pinfunction "7_7") (pintype "passive"))
      (node (ref "J3") (pin "8") (pinfunction "8_8") (pintype "passive"))
      (node (ref "J3") (pin "9") (pinfunction "9_9") (pintype "passive"))
      (node (ref "J4") (pin "7") (pinfunction "7_7") (pintype "passive"))
      (node (ref "J5") (pin "6") (pinfunction "6_6") (pintype "passive"))
      (node (ref "J5") (pin "7") (pinfunction "7_7") (pintype "passive"))
      (node (ref "J7") (pin "4") (pinfunction "4_4") (pintype "passive"))
      (node (ref "P2") (pin "8") (pintype "passive"))
      (node (ref "P6") (pin "A1") (pinfunction "GND_A1") (pintype "bidirectional"))
      (node (ref "P6") (pin "B1") (pinfunction "GND_B1") (pintype "bidirectional"))
      (node (ref "P7") (pin "A1") (pinfunction "GND_A1") (pintype "bidirectional"))
      (node (ref "P7") (pin "B1") (pinfunction "GND_B1") (pintype "bidirectional"))
      (node (ref "P9") (pin "A1") (pinfunction "GND_A1") (pintype "bidirectional"))
      (node (ref "P9") (pin "B1") (pinfunction "GND_B1") (pintype "bidirectional"))
      (node (ref "PWR") (pin "2") (pinfunction "K_2") (pintype "passive"))
      (node (ref "R10") (pin "2") (pinfunction "2_2") (pintype "passive"))
      (node (ref "R11") (pin "2") (pinfunction "2_2") (pintype "passive"))
      (node (ref "R18") (pin "1") (pinfunction "1_1") (pintype "passive"))
      (node (ref "R20") (pin "1") (pinfunction "1_1") (pintype "passive"))
      (node (ref "R21") (pin "1") (pinfunction "1_1") (pintype "passive"))
      (node (ref "R31") (pin "1") (pinfunction "1_1") (pintype "passive"))
      (node (ref "R8") (pin "1") (pinfunction "1_1") (pintype "passive"))
      (node (ref "R9") (pin "1") (pinfunction "1_1") (pintype "passive"))
      (node (ref "S1") (pin "3") (pinfunction "B1_3") (pintype "passive"))
      (node (ref "S2") (pin "3") (pinfunction "B1_3") (pintype "passive"))
      (node (ref "S5") (pin "2") (pinfunction "2_2") (pintype "passive"))
      (node (ref "U1") (pin "1") (pinfunction "GND_1") (pintype "passive"))
      (node (ref "U2") (pin "10") (pinfunction "VSS_5_10") (pintype "power_in"))
      (node (ref "U2") (pin "19") (pinfunction "VSSA_19") (pintype "power_in"))
      (node (ref "U2") (pin "27") (pinfunction "VSS_4_27") (pintype "power_in"))
      (node (ref "U2") (pin "49") (pinfunction "VSS_1_49") (pintype "power_in"))
      (node (ref "U2") (pin "74") (pinfunction "VSS_2_74") (pintype "power_in"))
      (node (ref "U2") (pin "99") (pinfunction "VSS_3_99") (pintype "power_in"))
      (node (ref "U3") (pin "18") (pinfunction "VSS/GND_18") (pintype "power_in"))
    )
    (net (code "123") (name "Net-(D2-K)") (class "Default")
      (node (ref "D2") (pin "2") (pinfunction "K_2") (pintype "passive"))
      (node (ref "R13") (pin "2") (pinfunction "2_2") (pintype "passive"))
    )
    (net (code "124") (name "Net-(D3-K)") (class "Default")
      (node (ref "D3") (pin "2") (pinfunction "K_2") (pintype "passive"))
      (node (ref "R21") (pin "2") (pinfunction "2_2") (pintype "passive"))
    )
    (net (code "125") (name "Net-(J3-Pad6)") (class "Default")
      (node (ref "J3") (pin "6") (pinfunction "6_6") (pintype "passive"))
      (node (ref "R5") (pin "1") (pinfunction "1_1") (pintype "passive"))
    )
    (net (code "126") (name "Net-(J3-Pad10)") (class "Default")
      (node (ref "J3") (pin "10") (pinfunction "10_10") (pintype "passive"))
      (node (ref "J5") (pin "1") (pinfunction "1_1") (pintype "passive"))
    )
    (net (code "127") (name "Net-(LED1-A)") (class "Default")
      (node (ref "LED1") (pin "1") (pinfunction "A_1") (pintype "passive"))
      (node (ref "R2") (pin "2") (pinfunction "2_2") (pintype "passive"))
    )
    (net (code "128") (name "Net-(LED2-A)") (class "Default")
      (node (ref "LED2") (pin "1") (pinfunction "A_1") (pintype "passive"))
      (node (ref "R3") (pin "2") (pinfunction "2_2") (pintype "passive"))
    )
    (net (code "129") (name "Net-(P2-Pad9)") (class "Default")
      (node (ref "P2") (pin "9") (pintype "passive"))
      (node (ref "R28") (pin "2") (pintype "passive"))
    )
    (net (code "130") (name "Net-(P2-Pad12)") (class "Default")
      (node (ref "P2") (pin "12") (pintype "passive"))
      (node (ref "R29") (pin "2") (pintype "passive"))
    )
    (net (code "131") (name "Net-(P6-CC-PadA5)") (class "Default")
      (node (ref "P6") (pin "A5") (pinfunction "CC_A5") (pintype "bidirectional"))
      (node (ref "R20") (pin "2") (pinfunction "2_2") (pintype "passive"))
    )
    (net (code "132") (name "Net-(P6-CC-PadB5)") (class "Default")
      (node (ref "P6") (pin "B5") (pinfunction "CC_B5") (pintype "bidirectional"))
      (node (ref "R31") (pin "2") (pinfunction "2_2") (pintype "passive"))
    )
    (net (code "133") (name "Net-(P7-CC-PadA5)") (class "Default")
      (node (ref "P7") (pin "A5") (pinfunction "CC_A5") (pintype "bidirectional"))
      (node (ref "R8") (pin "2") (pinfunction "2_2") (pintype "passive"))
    )
    (net (code "134") (name "Net-(P7-CC-PadB5)") (class "Default")
      (node (ref "P7") (pin "B5") (pinfunction "CC_B5") (pintype "bidirectional"))
      (node (ref "R9") (pin "2") (pinfunction "2_2") (pintype "passive"))
    )
    (net (code "135") (name "Net-(P9-CC-PadA5)") (class "Default")
      (node (ref "P9") (pin "A5") (pinfunction "CC_A5") (pintype "bidirectional"))
      (node (ref "R10") (pin "1") (pinfunction "1_1") (pintype "passive"))
    )
    (net (code "136") (name "Net-(P9-CC-PadB5)") (class "Default")
      (node (ref "P9") (pin "B5") (pinfunction "CC_B5") (pintype "bidirectional"))
      (node (ref "R11") (pin "1") (pinfunction "1_1") (pintype "passive"))
    )
    (net (code "137") (name "Net-(PWR-A)") (class "Default")
      (node (ref "PWR") (pin "1") (pinfunction "A_1") (pintype "passive"))
      (node (ref "R1") (pin "1") (pinfunction "1_1") (pintype "passive"))
    )
    (net (code "138") (name "Net-(U1-VOUT)") (class "Default")
      (node (ref "C13") (pin "1") (pinfunction "1_1") (pintype "passive"))
      (node (ref "S3") (pin "1") (pinfunction "1_1") (pintype "passive"))
      (node (ref "U1") (pin "2") (pinfunction "VOUT_2") (pintype "passive"))
    )
    (net (code "139") (name "unconnected-(P2-Pad7)") (class "Default")
      (node (ref "P2") (pin "7") (pintype "passive"))
    )
    (net (code "140") (name "unconnected-(P6-RFU1-PadA8)") (class "Default")
      (node (ref "P6") (pin "A8") (pinfunction "RFU1_A8") (pintype "bidirectional+no_connect"))
    )
    (net (code "141") (name "unconnected-(P6-RFU1-PadB8)") (class "Default")
      (node (ref "P6") (pin "B8") (pinfunction "RFU1_B8") (pintype "bidirectional+no_connect"))
    )
    (net (code "142") (name "unconnected-(P7-RFU1-PadA8)") (class "Default")
      (node (ref "P7") (pin "A8") (pinfunction "RFU1_A8") (pintype "bidirectional+no_connect"))
    )
    (net (code "143") (name "unconnected-(P7-RFU1-PadB8)") (class "Default")
      (node (ref "P7") (pin "B8") (pinfunction "RFU1_B8") (pintype "bidirectional+no_connect"))
    )
    (net (code "144") (name "unconnected-(P9-RFU1-PadA8)") (class "Default")
      (node (ref "P9") (pin "A8") (pinfunction "RFU1_A8") (pintype "bidirectional+no_connect"))
    )
    (net (code "145") (name "unconnected-(P9-RFU1-PadB8)") (class "Default")
      (node (ref "P9") (pin "B8") (pinfunction "RFU1_B8") (pintype "bidirectional+no_connect"))
    )
    (net (code "146") (name "unconnected-(S1-A1-Pad4)") (class "Default")
      (node (ref "S1") (pin "4") (pinfunction "A1_4") (pintype "passive"))
    )
    (net (code "147") (name "unconnected-(S1-B0-Pad2)") (class "Default")
      (node (ref "S1") (pin "2") (pinfunction "B0_2") (pintype "passive"))
    )
    (net (code "148") (name "unconnected-(S2-A1-Pad4)") (class "Default")
      (node (ref "S2") (pin "4") (pinfunction "A1_4") (pintype "passive"))
    )
    (net (code "149") (name "unconnected-(S2-B0-Pad2)") (class "Default")
      (node (ref "S2") (pin "2") (pinfunction "B0_2") (pintype "passive"))
    )
    (net (code "150") (name "unconnected-(S3-Pad2)") (class "Default")
      (node (ref "S3") (pin "2") (pinfunction "2_2") (pintype "passive"))
    )
    (net (code "151") (name "unconnected-(U3-PA5{slash}UART1_CTS{slash}PA1_(no5V)-Pad2)") (class "Default")
      (node (ref "U3") (pin "2") (pinfunction "PA5/UART1_CTS/PA1_(no5V)_2") (pintype "bidirectional+no_connect"))
    )
    (net (code "152") (name "unconnected-(U3-PB12{slash}SPI2_NSS{slash}CAN2_RX-Pad5)") (class "Default")
      (node (ref "U3") (pin "5") (pinfunction "PB12/SPI2_NSS/CAN2_RX_5") (pintype "bidirectional+no_connect"))
    )
    (net (code "153") (name "unconnected-(U3-PB14{slash}SPI2_MISO{slash}UART3_RTS-Pad7)") (class "Default")
      (node (ref "U3") (pin "7") (pinfunction "PB14/SPI2_MISO/UART3_RTS_7") (pintype "bidirectional+no_connect"))
    )
    (net (code "154") (name "unconnected-(U3-PB15{slash}SPI2_MOSI{slash}UART1_TX-Pad8)") (class "Default")
      (node (ref "U3") (pin "8") (pinfunction "PB15/SPI2_MOSI/UART1_TX_8") (pintype "bidirectional+no_connect"))
    )
  )
)
